# microcontroller.net
KiCad netlist of a schematic drawn in Altium Designer
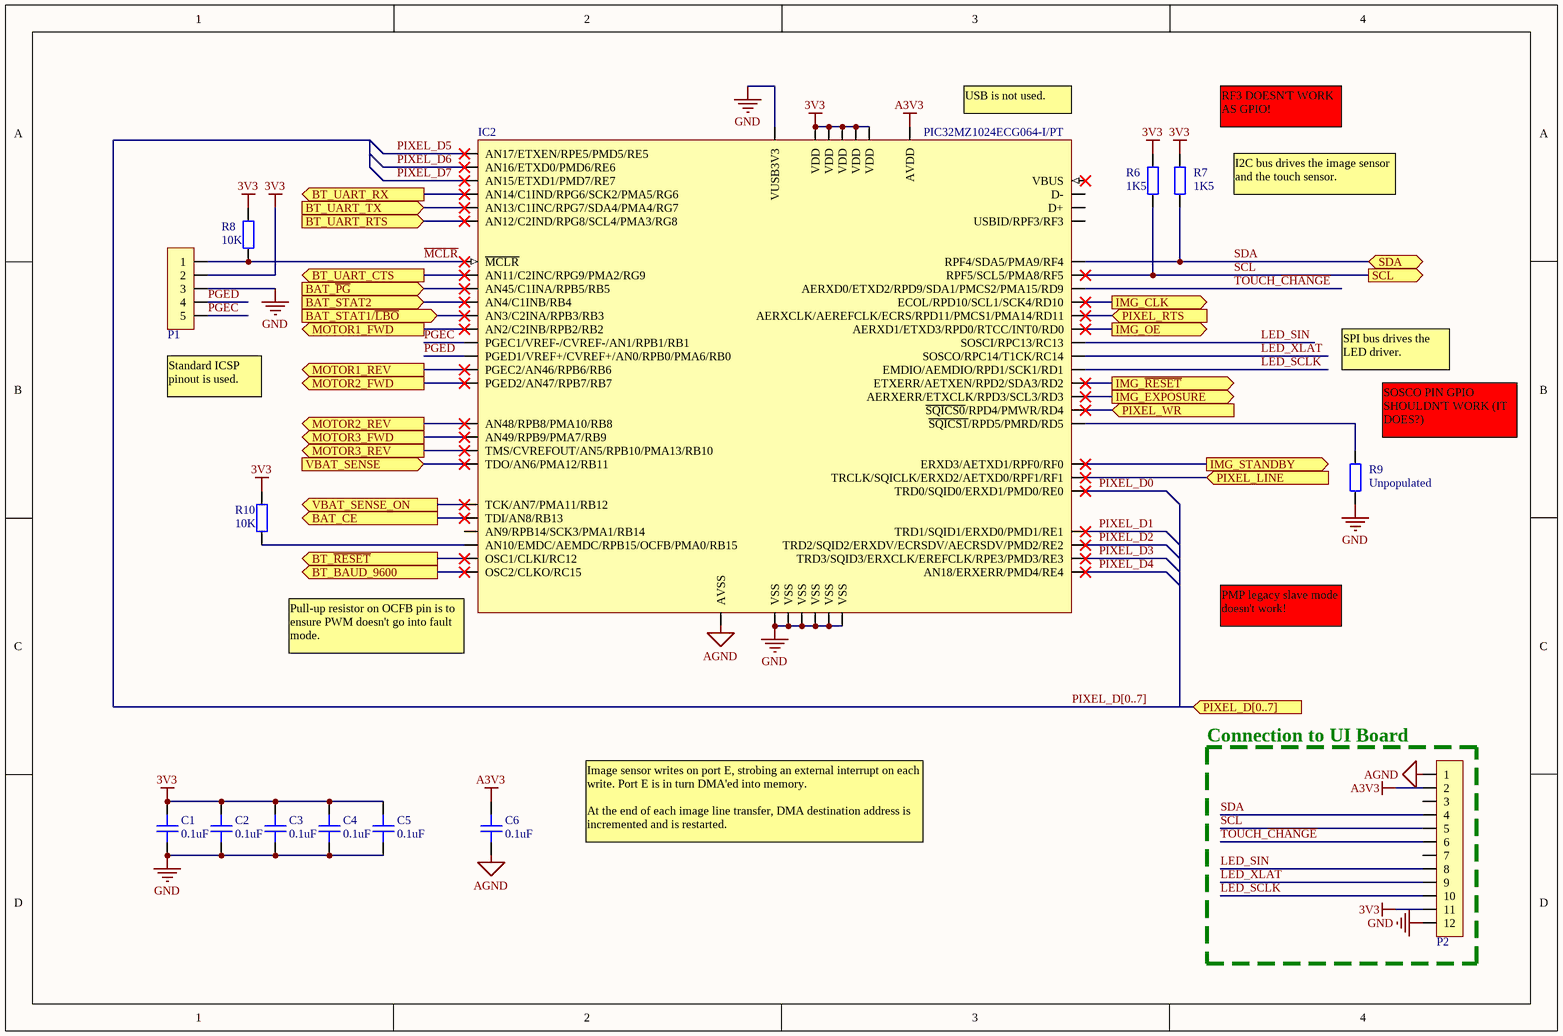
[diagram p0: microcontroller.SchDoc]

(export (version "E")
  (design (tool "Eeschema 10.0.6"))
  (components
    (comp (ref "C1")
      (value "0.1uF")
      (footprint "TwoTerminal:1608[0603]_M")
      (description "Generic Capacitor")
      (libsource (lib "Passive") (part "Capacitor"))
    )
    (comp (ref "C2")
      (value "0.1uF")
      (footprint "TwoTerminal:1608[0603]_M")
      (description "Generic Capacitor")
      (libsource (lib "Passive") (part "Capacitor"))
    )
    (comp (ref "C3")
      (value "0.1uF")
      (footprint "TwoTerminal:1608[0603]_M")
      (description "Generic Capacitor")
      (libsource (lib "Passive") (part "Capacitor"))
    )
    (comp (ref "C4")
      (value "0.1uF")
      (footprint "TwoTerminal:1608[0603]_M")
      (description "Generic Capacitor")
      (libsource (lib "Passive") (part "Capacitor"))
    )
    (comp (ref "C5")
      (value "0.1uF")
      (footprint "TwoTerminal:1608[0603]_M")
      (description "Generic Capacitor")
      (libsource (lib "Passive") (part "Capacitor"))
    )
    (comp (ref "C6")
      (value "0.1uF")
      (footprint "TwoTerminal:1608[0603]_M")
      (description "Generic Capacitor")
      (libsource (lib "Passive") (part "Capacitor"))
    )
    (comp (ref "IC2")
      (value "PIC32MZ1024ECG064-I/PT")
      (footprint "TQFP-64_M")
      (description "32-bit Microcontroller")
      (libsource (lib "PIC") (part "PIC32MZ1024ECG064"))
    )
    (comp (ref "P1")
      (value "Connector 5")
      (footprint "BM05B-SRSS_N")
      (description "Connector 5-Pin")
      (libsource (lib "Connector") (part "Connector 5"))
    )
    (comp (ref "P2")
      (value "Connector 12")
      (footprint "FH33-12S-0.5SH_N")
      (description "Connector 12-Pin")
      (libsource (lib "Connector") (part "Connector 12"))
    )
    (comp (ref "R6")
      (value "1K5")
      (footprint "TwoTerminal:1608[0603]_M")
      (description "Generic Resistor")
      (libsource (lib "Passive") (part "Resistor"))
    )
    (comp (ref "R7")
      (value "1K5")
      (footprint "TwoTerminal:1608[0603]_M")
      (description "Generic Resistor")
      (libsource (lib "Passive") (part "Resistor"))
    )
    (comp (ref "R8")
      (value "10K")
      (footprint "TwoTerminal:1608[0603]_M")
      (description "Generic Resistor")
      (libsource (lib "Passive") (part "Resistor"))
    )
    (comp (ref "R9")
      (value "Unpopulated")
      (footprint "TwoTerminal:1608[0603]_M")
      (description "Generic Resistor")
      (libsource (lib "Passive") (part "Resistor"))
    )
    (comp (ref "R10")
      (value "10K")
      (footprint "TwoTerminal:1608[0603]_M")
      (description "Generic Resistor")
      (libsource (lib "Passive") (part "Resistor"))
    )
  )
  (nets
    (net (code "1") (name "/BAT_CE") (class "Default")
      (node (ref "IC2") (pin "28") (pinfunction "TDI/AN8/RB13_28") (pintype "bidirectional+no_connect"))
    )
    (net (code "2") (name "/BAT_STAT1{slash}~{LBO}") (class "Default")
      (node (ref "IC2") (pin "13") (pinfunction "AN3/C2INA/RPB3/RB3_13") (pintype "bidirectional+no_connect"))
    )
    (net (code "3") (name "/BAT_STAT2") (class "Default")
      (node (ref "IC2") (pin "12") (pinfunction "AN4/C1INB/RB4_12") (pintype "bidirectional+no_connect"))
    )
    (net (code "4") (name "/BAT_~{PG}") (class "Default")
      (node (ref "IC2") (pin "11") (pinfunction "AN45/C1INA/RPB5/RB5_11") (pintype "bidirectional+no_connect"))
    )
    (net (code "5") (name "/BT_BAUD_9600") (class "Default")
      (node (ref "IC2") (pin "32") (pinfunction "OSC2/CLKO/RC15_32") (pintype "bidirectional+no_connect"))
    )
    (net (code "6") (name "/BT_UART_CTS") (class "Default")
      (node (ref "IC2") (pin "10") (pinfunction "AN11/C2INC/RPG9/PMA2/RG9_10") (pintype "bidirectional+no_connect"))
    )
    (net (code "7") (name "/BT_UART_RTS") (class "Default")
      (node (ref "IC2") (pin "6") (pinfunction "AN12/C2IND/RPG8/SCL4/PMA3/RG8_6") (pintype "bidirectional+no_connect"))
    )
    (net (code "8") (name "/BT_UART_RX") (class "Default")
      (node (ref "IC2") (pin "4") (pinfunction "AN14/C1IND/RPG6/SCK2/PMA5/RG6_4") (pintype "bidirectional+no_connect"))
    )
    (net (code "9") (name "/BT_UART_TX") (class "Default")
      (node (ref "IC2") (pin "5") (pinfunction "AN13/C1INC/RPG7/SDA4/PMA4/RG7_5") (pintype "bidirectional+no_connect"))
    )
    (net (code "10") (name "/BT_~{RESET}") (class "Default")
      (node (ref "IC2") (pin "31") (pinfunction "OSC1/CLKI/RC12_31") (pintype "bidirectional+no_connect"))
    )
    (net (code "11") (name "/IMG_CLK") (class "Default")
      (node (ref "IC2") (pin "44") (pinfunction "ECOL/RPD10/SCL1/SCK4/RD10_44") (pintype "bidirectional+no_connect"))
    )
    (net (code "12") (name "/IMG_EXPOSURE") (class "Default")
      (node (ref "IC2") (pin "51") (pinfunction "AERXERR/ETXCLK/RPD3/SCL3/RD3_51") (pintype "bidirectional+no_connect"))
    )
    (net (code "13") (name "/IMG_OE") (class "Default")
      (node (ref "IC2") (pin "46") (pinfunction "AERXD1/ETXD3/RPD0/RTCC/INT0/RD0_46") (pintype "bidirectional+no_connect"))
    )
    (net (code "14") (name "/IMG_STANDBY") (class "Default")
      (node (ref "IC2") (pin "56") (pinfunction "ERXD3/AETXD1/RPF0/RF0_56") (pintype "bidirectional+no_connect"))
    )
    (net (code "15") (name "/IMG_~{RESET}") (class "Default")
      (node (ref "IC2") (pin "50") (pinfunction "ETXERR/AETXEN/RPD2/SDA3/RD2_50") (pintype "bidirectional+no_connect"))
    )
    (net (code "16") (name "/LED_SCLK") (class "Default")
      (node (ref "IC2") (pin "49") (pinfunction "EMDIO/AEMDIO/RPD1/SCK1/RD1_49") (pintype "bidirectional"))
      (node (ref "P2") (pin "10") (pinfunction "10_10") (pintype "passive"))
    )
    (net (code "17") (name "/LED_SIN") (class "Default")
      (node (ref "IC2") (pin "47") (pinfunction "SOSCI/RPC13/RC13_47") (pintype "bidirectional"))
      (node (ref "P2") (pin "8") (pinfunction "8_8") (pintype "passive"))
    )
    (net (code "18") (name "/LED_XLAT") (class "Default")
      (node (ref "IC2") (pin "48") (pinfunction "SOSCO/RPC14/T1CK/RC14_48") (pintype "bidirectional"))
      (node (ref "P2") (pin "9") (pinfunction "9_9") (pintype "passive"))
    )
    (net (code "19") (name "/MOTOR1_FWD") (class "Default")
      (node (ref "IC2") (pin "14") (pinfunction "AN2/C2INB/RPB2/RB2_14") (pintype "bidirectional+no_connect"))
    )
    (net (code "20") (name "/MOTOR1_REV") (class "Default")
      (node (ref "IC2") (pin "17") (pinfunction "PGEC2/AN46/RPB6/RB6_17") (pintype "bidirectional+no_connect"))
    )
    (net (code "21") (name "/MOTOR2_FWD") (class "Default")
      (node (ref "IC2") (pin "18") (pinfunction "PGED2/AN47/RPB7/RB7_18") (pintype "bidirectional+no_connect"))
    )
    (net (code "22") (name "/MOTOR2_REV") (class "Default")
      (node (ref "IC2") (pin "21") (pinfunction "AN48/RPB8/PMA10/RB8_21") (pintype "bidirectional+no_connect"))
    )
    (net (code "23") (name "/MOTOR3_FWD") (class "Default")
      (node (ref "IC2") (pin "22") (pinfunction "AN49/RPB9/PMA7/RB9_22") (pintype "bidirectional+no_connect"))
    )
    (net (code "24") (name "/MOTOR3_REV") (class "Default")
      (node (ref "IC2") (pin "23") (pinfunction "TMS/CVREFOUT/AN5/RPB10/PMA13/RB10_23") (pintype "bidirectional+no_connect"))
    )
    (net (code "25") (name "/PGEC") (class "Default")
      (node (ref "IC2") (pin "15") (pinfunction "PGEC1/VREF-/CVREF-/AN1/RPB1/RB1_15") (pintype "bidirectional"))
      (node (ref "P1") (pin "5") (pinfunction "5_5") (pintype "passive"))
    )
    (net (code "26") (name "/PGED") (class "Default")
      (node (ref "IC2") (pin "16") (pinfunction "PGED1/VREF+/CVREF+/AN0/RPB0/PMA6/RB0_16") (pintype "bidirectional"))
      (node (ref "P1") (pin "4") (pinfunction "4_4") (pintype "passive"))
    )
    (net (code "27") (name "/PIXEL_D0") (class "Default")
      (node (ref "IC2") (pin "58") (pinfunction "TRD0/SQID0/ERXD1/PMD0/RE0_58") (pintype "bidirectional+no_connect"))
    )
    (net (code "28") (name "/PIXEL_D1") (class "Default")
      (node (ref "IC2") (pin "61") (pinfunction "TRD1/SQID1/ERXD0/PMD1/RE1_61") (pintype "bidirectional+no_connect"))
    )
    (net (code "29") (name "/PIXEL_D2") (class "Default")
      (node (ref "IC2") (pin "62") (pinfunction "TRD2/SQID2/ERXDV/ECRSDV/AECRSDV/PMD2/RE2_62") (pintype "bidirectional+no_connect"))
    )
    (net (code "30") (name "/PIXEL_D3") (class "Default")
      (node (ref "IC2") (pin "63") (pinfunction "TRD3/SQID3/ERXCLK/EREFCLK/RPE3/PMD3/RE3_63") (pintype "bidirectional+no_connect"))
    )
    (net (code "31") (name "/PIXEL_D4") (class "Default")
      (node (ref "IC2") (pin "64") (pinfunction "AN18/ERXERR/PMD4/RE4_64") (pintype "bidirectional+no_connect"))
    )
    (net (code "32") (name "/PIXEL_D5") (class "Default")
      (node (ref "IC2") (pin "1") (pinfunction "AN17/ETXEN/RPE5/PMD5/RE5_1") (pintype "bidirectional+no_connect"))
    )
    (net (code "33") (name "/PIXEL_D6") (class "Default")
      (node (ref "IC2") (pin "2") (pinfunction "AN16/ETXD0/PMD6/RE6_2") (pintype "bidirectional+no_connect"))
    )
    (net (code "34") (name "/PIXEL_D7") (class "Default")
      (node (ref "IC2") (pin "3") (pinfunction "AN15/ETXD1/PMD7/RE7_3") (pintype "bidirectional+no_connect"))
    )
    (net (code "36") (name "/PIXEL_LINE") (class "Default")
      (node (ref "IC2") (pin "57") (pinfunction "TRCLK/SQICLK/ERXD2/AETXD0/RPF1/RF1_57") (pintype "bidirectional+no_connect"))
    )
    (net (code "37") (name "/PIXEL_RTS") (class "Default")
      (node (ref "IC2") (pin "45") (pinfunction "AERXCLK/AEREFCLK/ECRS/RPD11/PMCS1/PMA14/RD11_45") (pintype "bidirectional+no_connect"))
    )
    (net (code "38") (name "/PIXEL_WR") (class "Default")
      (node (ref "IC2") (pin "52") (pinfunction "~{SQICS0}/RPD4/PMWR/RD4_52") (pintype "bidirectional+no_connect"))
    )
    (net (code "39") (name "/SCL") (class "Default")
      (node (ref "IC2") (pin "42") (pinfunction "RPF5/SCL5/PMA8/RF5_42") (pintype "bidirectional"))
      (node (ref "P2") (pin "5") (pinfunction "5_5") (pintype "passive"))
      (node (ref "R6") (pin "1") (pinfunction "1_1") (pintype "passive"))
    )
    (net (code "40") (name "/SDA") (class "Default")
      (node (ref "IC2") (pin "41") (pinfunction "RPF4/SDA5/PMA9/RF4_41") (pintype "bidirectional"))
      (node (ref "P2") (pin "4") (pinfunction "4_4") (pintype "passive"))
      (node (ref "R7") (pin "1") (pinfunction "1_1") (pintype "passive"))
    )
    (net (code "41") (name "/TOUCH_~{CHANGE}") (class "Default")
      (node (ref "IC2") (pin "43") (pinfunction "AERXD0/ETXD2/RPD9/SDA1/PMCS2/PMA15/RD9_43") (pintype "bidirectional"))
      (node (ref "P2") (pin "6") (pinfunction "6_6") (pintype "passive"))
    )
    (net (code "42") (name "/VBAT_SENSE") (class "Default")
      (node (ref "IC2") (pin "24") (pinfunction "TDO/AN6/PMA12/RB11_24") (pintype "bidirectional+no_connect"))
    )
    (net (code "43") (name "/VBAT_SENSE_ON") (class "Default")
      (node (ref "IC2") (pin "27") (pinfunction "TCK/AN7/PMA11/RB12_27") (pintype "bidirectional+no_connect"))
    )
    (net (code "44") (name "/~{MCLR}") (class "Default")
      (node (ref "IC2") (pin "9") (pinfunction "~{MCLR}_9") (pintype "input"))
      (node (ref "P1") (pin "1") (pinfunction "1_1") (pintype "passive"))
      (node (ref "R8") (pin "1") (pinfunction "1_1") (pintype "passive"))
    )
    (net (code "45") (name "3V3") (class "Default")
      (node (ref "C1") (pin "2") (pinfunction "2_2") (pintype "passive"))
      (node (ref "C2") (pin "2") (pinfunction "2_2") (pintype "passive"))
      (node (ref "C3") (pin "2") (pinfunction "2_2") (pintype "passive"))
      (node (ref "C4") (pin "2") (pinfunction "2_2") (pintype "passive"))
      (node (ref "C5") (pin "2") (pinfunction "2_2") (pintype "passive"))
      (node (ref "IC2") (pin "26") (pinfunction "VDD_26") (pintype "power_in"))
      (node (ref "IC2") (pin "39") (pinfunction "VDD_39") (pintype "power_in"))
      (node (ref "IC2") (pin "54") (pinfunction "VDD_54") (pintype "power_in"))
      (node (ref "IC2") (pin "60") (pinfunction "VDD_60") (pintype "power_in"))
      (node (ref "IC2") (pin "8") (pinfunction "VDD_8") (pintype "power_in"))
      (node (ref "P1") (pin "2") (pinfunction "2_2") (pintype "passive"))
      (node (ref "P2") (pin "11") (pinfunction "11_11") (pintype "passive"))
      (node (ref "R10") (pin "2") (pinfunction "2_2") (pintype "passive"))
      (node (ref "R6") (pin "2") (pinfunction "2_2") (pintype "passive"))
      (node (ref "R7") (pin "2") (pinfunction "2_2") (pintype "passive"))
      (node (ref "R8") (pin "2") (pinfunction "2_2") (pintype "passive"))
    )
    (net (code "46") (name "A3V3") (class "Default")
      (node (ref "C6") (pin "2") (pinfunction "2_2") (pintype "passive"))
      (node (ref "IC2") (pin "19") (pinfunction "AVDD_19") (pintype "power_in"))
      (node (ref "P2") (pin "2") (pinfunction "2_2") (pintype "passive"))
    )
    (net (code "47") (name "AGND") (class "Default")
      (node (ref "C6") (pin "1") (pinfunction "1_1") (pintype "passive"))
      (node (ref "IC2") (pin "20") (pinfunction "AVSS_20") (pintype "power_in"))
      (node (ref "P2") (pin "1") (pinfunction "1_1") (pintype "passive"))
    )
    (net (code "48") (name "GND") (class "Default")
      (node (ref "C1") (pin "1") (pinfunction "1_1") (pintype "passive"))
      (node (ref "C2") (pin "1") (pinfunction "1_1") (pintype "passive"))
      (node (ref "C3") (pin "1") (pinfunction "1_1") (pintype "passive"))
      (node (ref "C4") (pin "1") (pinfunction "1_1") (pintype "passive"))
      (node (ref "C5") (pin "1") (pinfunction "1_1") (pintype "passive"))
      (node (ref "IC2") (pin "25") (pinfunction "VSS_25") (pintype "power_in"))
      (node (ref "IC2") (pin "34") (pinfunction "VUSB3V3_34") (pintype "power_in"))
      (node (ref "IC2") (pin "35") (pinfunction "VSS_35") (pintype "power_in"))
      (node (ref "IC2") (pin "40") (pinfunction "VSS_40") (pintype "power_in"))
      (node (ref "IC2") (pin "55") (pinfunction "VSS_55") (pintype "power_in"))
      (node (ref "IC2") (pin "59") (pinfunction "VSS_59") (pintype "power_in"))
      (node (ref "IC2") (pin "7") (pinfunction "VSS_7") (pintype "power_in"))
      (node (ref "P1") (pin "3") (pinfunction "3_3") (pintype "passive"))
      (node (ref "P2") (pin "12") (pinfunction "12_12") (pintype "passive"))
      (node (ref "R9") (pin "1") (pinfunction "1_1") (pintype "passive"))
    )
    (net (code "49") (name "Net-(IC2-AN10{slash}EMDC{slash}AEMDC{slash}RPB15{slash}OCFB{slash}PMA0{slash}RB15)") (class "Default")
      (node (ref "IC2") (pin "30") (pinfunction "AN10/EMDC/AEMDC/RPB15/OCFB/PMA0/RB15_30") (pintype "bidirectional"))
      (node (ref "R10") (pin "1") (pinfunction "1_1") (pintype "passive"))
    )
    (net (code "50") (name "Net-(IC2-~{SQICS1}{slash}RPD5{slash}PMRD{slash}RD5)") (class "Default")
      (node (ref "IC2") (pin "53") (pinfunction "~{SQICS1}/RPD5/PMRD/RD5_53") (pintype "bidirectional"))
      (node (ref "R9") (pin "2") (pinfunction "2_2") (pintype "passive"))
    )
    (net (code "51") (name "unconnected-(IC2-AN9{slash}RPB14{slash}SCK3{slash}PMA1{slash}RB14-Pad29)") (class "Default")
      (node (ref "IC2") (pin "29") (pinfunction "AN9/RPB14/SCK3/PMA1/RB14_29") (pintype "bidirectional"))
    )
    (net (code "52") (name "unconnected-(IC2-D+-Pad37)") (class "Default")
      (node (ref "IC2") (pin "37") (pinfunction "D+_37") (pintype "bidirectional"))
    )
    (net (code "53") (name "unconnected-(IC2-D--Pad36)") (class "Default")
      (node (ref "IC2") (pin "36") (pinfunction "D-_36") (pintype "bidirectional"))
    )
    (net (code "54") (name "unconnected-(IC2-USBID{slash}RPF3{slash}RF3-Pad38)") (class "Default")
      (node (ref "IC2") (pin "38") (pinfunction "USBID/RPF3/RF3_38") (pintype "bidirectional"))
    )
    (net (code "55") (name "unconnected-(IC2-VBUS-Pad33)") (class "Default")
      (node (ref "IC2") (pin "33") (pinfunction "VBUS_33") (pintype "input+no_connect"))
    )
    (net (code "56") (name "unconnected-(P2-Pad3)") (class "Default")
      (node (ref "P2") (pin "3") (pinfunction "3_3") (pintype "passive"))
    )
    (net (code "57") (name "unconnected-(P2-Pad7)") (class "Default")
      (node (ref "P2") (pin "7") (pinfunction "7_7") (pintype "passive"))
    )
  )
)
